# Project.net
KiCad netlist of a schematic drawn in EAGLE
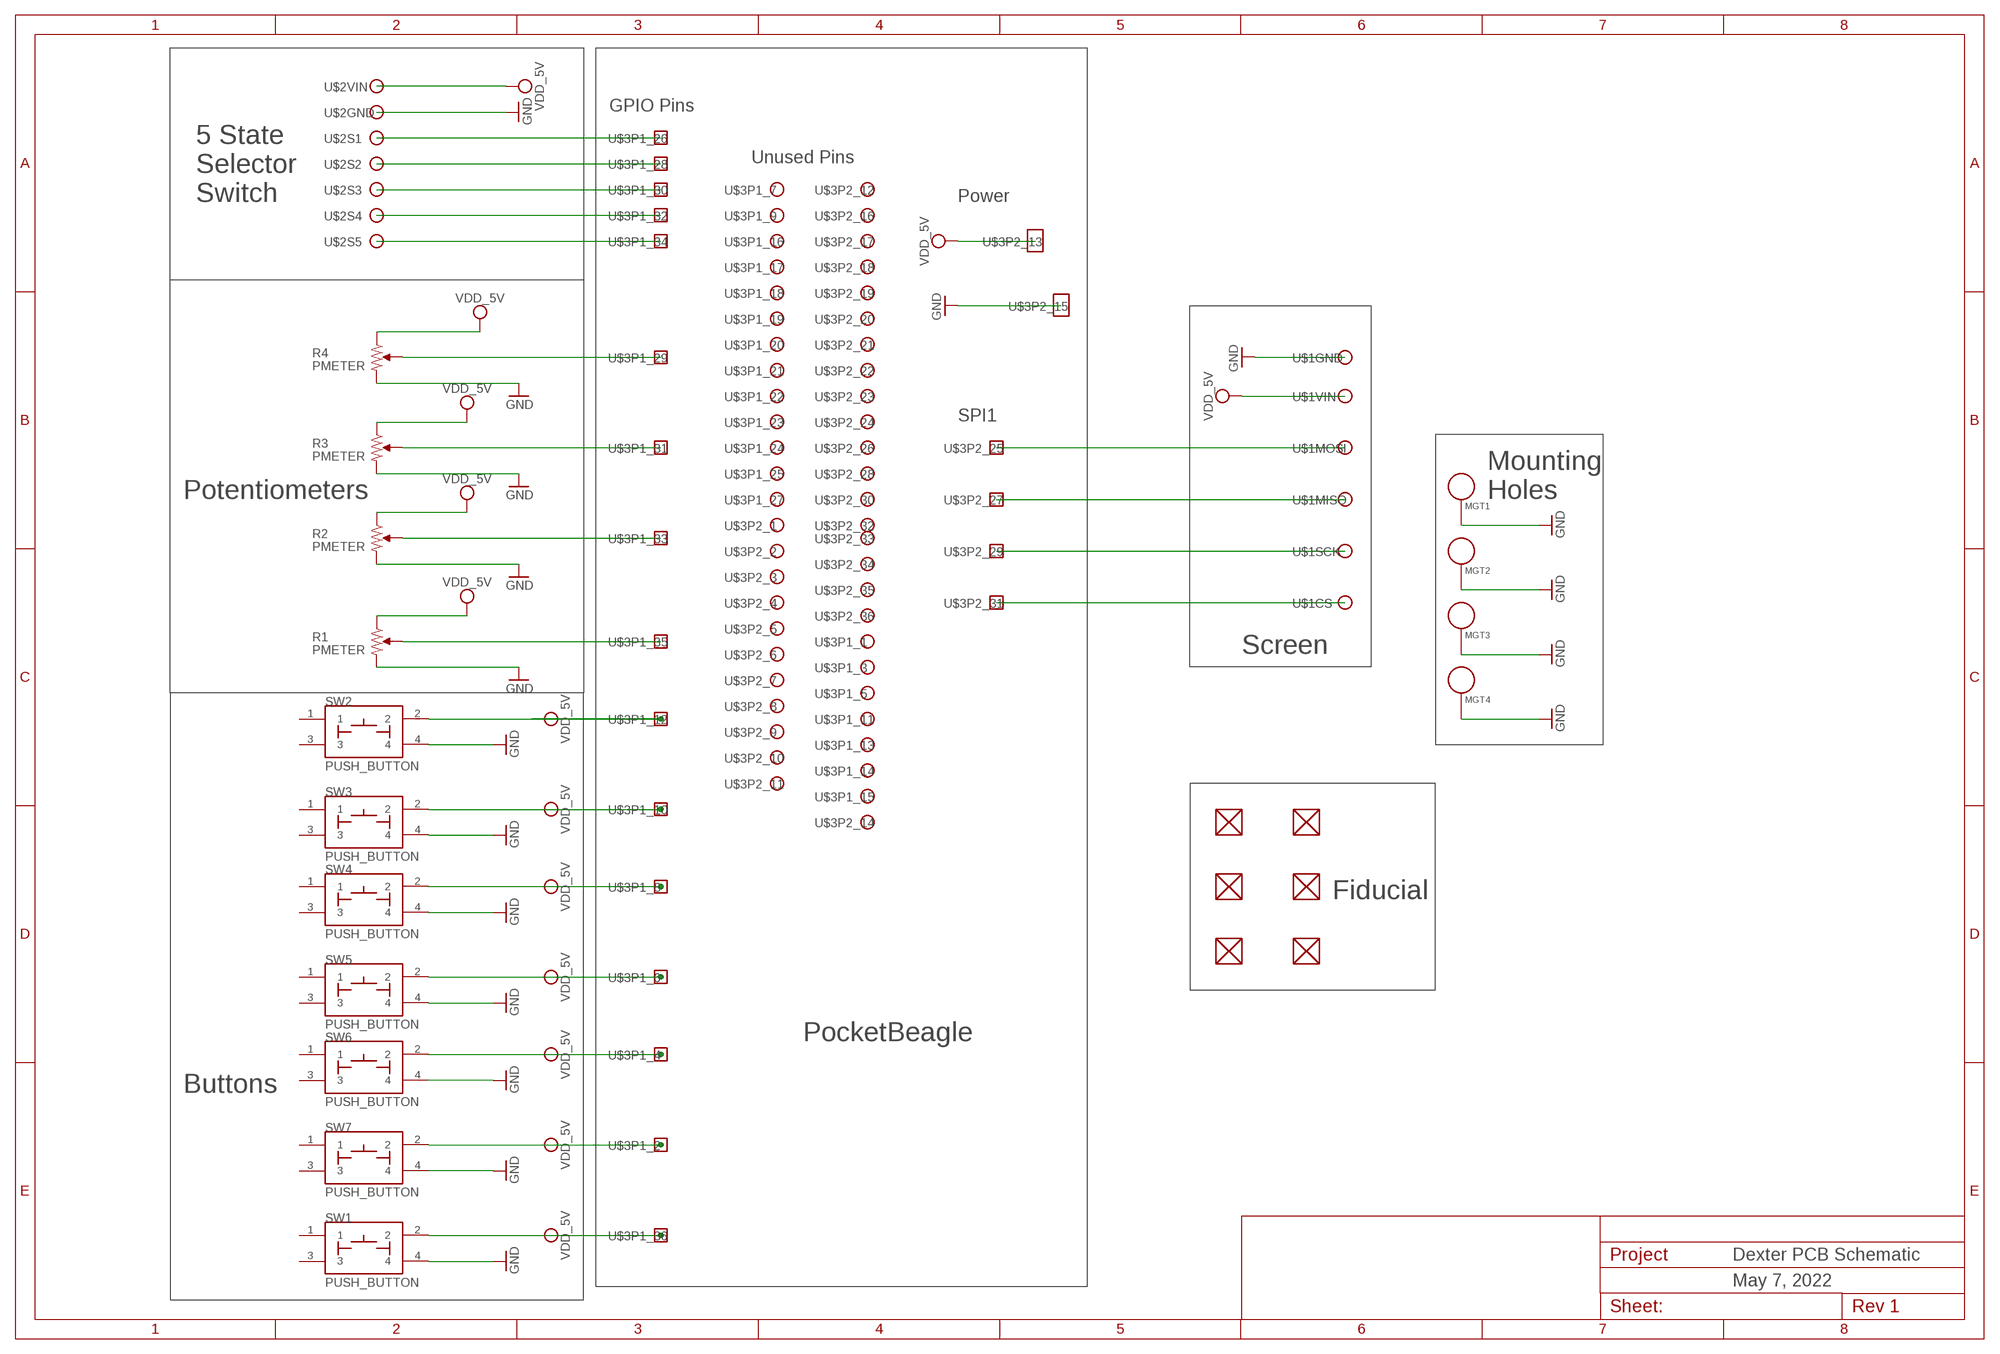
[diagram p0: schematic, sheet 1]

(export (version "E")
  (design (tool "Eeschema 10.0.6"))
  (components
    (comp (ref "FUD1")
      (value "FIDUCIAL")
      (footprint "eagle-import:FIDUCIAL_40MIL")
      (libsource (lib "eagle-import") (part "FIDUCIAL"))
    )
    (comp (ref "FUD2")
      (value "FIDUCIAL")
      (footprint "eagle-import:FIDUCIAL_40MIL")
      (libsource (lib "eagle-import") (part "FIDUCIAL"))
    )
    (comp (ref "FUD3")
      (value "FIDUCIAL")
      (footprint "eagle-import:FIDUCIAL_40MIL")
      (libsource (lib "eagle-import") (part "FIDUCIAL"))
    )
    (comp (ref "FUD4")
      (value "FIDUCIAL")
      (footprint "eagle-import:FIDUCIAL_40MIL")
      (libsource (lib "eagle-import") (part "FIDUCIAL"))
    )
    (comp (ref "FUD5")
      (value "FIDUCIAL")
      (footprint "eagle-import:FIDUCIAL_40MIL")
      (libsource (lib "eagle-import") (part "FIDUCIAL"))
    )
    (comp (ref "FUD6")
      (value "FIDUCIAL")
      (footprint "eagle-import:FIDUCIAL_40MIL")
      (libsource (lib "eagle-import") (part "FIDUCIAL"))
    )
    (comp (ref "MGT1")
      (value "MOUNTING_HOLE")
      (footprint "eagle-import:MOUNTING_HOLE")
      (libsource (lib "eagle-import") (part "MOUNTING_HOLE"))
    )
    (comp (ref "MGT2")
      (value "MOUNTING_HOLE")
      (footprint "eagle-import:MOUNTING_HOLE")
      (libsource (lib "eagle-import") (part "MOUNTING_HOLE"))
    )
    (comp (ref "MGT3")
      (value "MOUNTING_HOLE")
      (footprint "eagle-import:MOUNTING_HOLE")
      (libsource (lib "eagle-import") (part "MOUNTING_HOLE"))
    )
    (comp (ref "MGT4")
      (value "MOUNTING_HOLE")
      (footprint "eagle-import:MOUNTING_HOLE")
      (libsource (lib "eagle-import") (part "MOUNTING_HOLE"))
    )
    (comp (ref "R1")
      (value "PMETER")
      (footprint "eagle-import:POT-PO90S")
      (libsource (lib "eagle-import") (part "PMETER"))
    )
    (comp (ref "R2")
      (value "PMETER")
      (footprint "eagle-import:POT-PO90S")
      (libsource (lib "eagle-import") (part "PMETER"))
    )
    (comp (ref "R3")
      (value "PMETER")
      (footprint "eagle-import:POT-PO90S")
      (libsource (lib "eagle-import") (part "PMETER"))
    )
    (comp (ref "R4")
      (value "PMETER")
      (footprint "eagle-import:POT-PO90S")
      (libsource (lib "eagle-import") (part "PMETER"))
    )
    (comp (ref "SW1")
      (value "PUSH_BUTTON")
      (footprint "eagle-import:BUTTON_12.5MM")
      (libsource (lib "eagle-import") (part "PUSH_BUTTON"))
    )
    (comp (ref "SW2")
      (value "PUSH_BUTTON")
      (footprint "eagle-import:BUTTON_12.5MM")
      (libsource (lib "eagle-import") (part "PUSH_BUTTON"))
    )
    (comp (ref "SW3")
      (value "PUSH_BUTTON")
      (footprint "eagle-import:BUTTON_12.5MM")
      (libsource (lib "eagle-import") (part "PUSH_BUTTON"))
    )
    (comp (ref "SW4")
      (value "PUSH_BUTTON")
      (footprint "eagle-import:BUTTON_12.5MM")
      (libsource (lib "eagle-import") (part "PUSH_BUTTON"))
    )
    (comp (ref "SW5")
      (value "PUSH_BUTTON")
      (footprint "eagle-import:BUTTON_12.5MM")
      (libsource (lib "eagle-import") (part "PUSH_BUTTON"))
    )
    (comp (ref "SW6")
      (value "PUSH_BUTTON")
      (footprint "eagle-import:BUTTON_12.5MM")
      (libsource (lib "eagle-import") (part "PUSH_BUTTON"))
    )
    (comp (ref "SW7")
      (value "PUSH_BUTTON")
      (footprint "eagle-import:BUTTON_12.5MM")
      (libsource (lib "eagle-import") (part "PUSH_BUTTON"))
    )
    (comp (ref "U$1")
      (value "SCREEN")
      (footprint "eagle-import:SCREEN")
      (libsource (lib "eagle-import") (part "SCREEN"))
    )
    (comp (ref "U$2")
      (value "SELECTOR_SWITCH")
      (footprint "eagle-import:SELECTOR_SWITCH")
      (libsource (lib "eagle-import") (part "SELECTOR_SWITCH"))
    )
    (comp (ref "U$3")
      (value "POCKETBEAGLE")
      (footprint "eagle-import:POCKETBEAGLE")
      (libsource (lib "eagle-import") (part "POCKETBEAGLE"))
    )
  )
  (nets
    (net (code "1") (name "GND") (class "Default")
      (node (ref "MGT1") (pin "P$1") (pinfunction "P$1_P$1") (pintype "bidirectional"))
      (node (ref "MGT2") (pin "P$1") (pinfunction "P$1_P$1") (pintype "bidirectional"))
      (node (ref "MGT3") (pin "P$1") (pinfunction "P$1_P$1") (pintype "bidirectional"))
      (node (ref "MGT4") (pin "P$1") (pinfunction "P$1_P$1") (pintype "bidirectional"))
      (node (ref "R1") (pin "CW") (pinfunction "CW_CW") (pintype "passive"))
      (node (ref "R2") (pin "CW") (pinfunction "CW_CW") (pintype "passive"))
      (node (ref "R3") (pin "CW") (pinfunction "CW_CW") (pintype "passive"))
      (node (ref "R4") (pin "CW") (pinfunction "CW_CW") (pintype "passive"))
      (node (ref "SW1") (pin "4") (pinfunction "4_4") (pintype "bidirectional"))
      (node (ref "SW2") (pin "4") (pinfunction "4_4") (pintype "bidirectional"))
      (node (ref "SW3") (pin "4") (pinfunction "4_4") (pintype "bidirectional"))
      (node (ref "SW4") (pin "4") (pinfunction "4_4") (pintype "bidirectional"))
      (node (ref "SW5") (pin "4") (pinfunction "4_4") (pintype "bidirectional"))
      (node (ref "SW6") (pin "4") (pinfunction "4_4") (pintype "bidirectional"))
      (node (ref "SW7") (pin "4") (pinfunction "4_4") (pintype "bidirectional"))
      (node (ref "U$1") (pin "1@JP1") (pinfunction "PWR_1@JP1") (pintype "bidirectional"))
      (node (ref "U$2") (pin "P$2") (pinfunction "PWR_P$2") (pintype "bidirectional"))
      (node (ref "U$3") (pin "15@P2") (pinfunction "PWR_15@P2") (pintype "bidirectional"))
    )
    (net (code "2") (name "Net-(U$1A-PWR)") (class "Default")
      (node (ref "U$1") (pin "5@JP1") (pinfunction "PWR_5@JP1") (pintype "bidirectional"))
      (node (ref "U$3") (pin "31@P2") (pinfunction "PWR_31@P2") (pintype "bidirectional"))
    )
    (net (code "3") (name "Net-(U$1C-PWR)") (class "Default")
      (node (ref "U$1") (pin "7@JP1") (pinfunction "PWR_7@JP1") (pintype "bidirectional"))
      (node (ref "U$3") (pin "27@P2") (pinfunction "PWR_27@P2") (pintype "bidirectional"))
    )
    (net (code "4") (name "Net-(U$1D-PWR)") (class "Default")
      (node (ref "U$1") (pin "6@JP1") (pinfunction "PWR_6@JP1") (pintype "bidirectional"))
      (node (ref "U$3") (pin "25@P2") (pinfunction "PWR_25@P2") (pintype "bidirectional"))
    )
    (net (code "5") (name "Net-(U$1E-PWR)") (class "Default")
      (node (ref "U$1") (pin "8@JP1") (pinfunction "PWR_8@JP1") (pintype "bidirectional"))
      (node (ref "U$3") (pin "29@P2") (pinfunction "PWR_29@P2") (pintype "bidirectional"))
    )
    (net (code "6") (name "Net-(U$2B-PWR)") (class "Default")
      (node (ref "U$2") (pin "P$3") (pinfunction "PWR_P$3") (pintype "bidirectional"))
      (node (ref "U$3") (pin "26@P1") (pinfunction "PWR_26@P1") (pintype "bidirectional"))
    )
    (net (code "7") (name "Net-(U$2C-PWR)") (class "Default")
      (node (ref "U$2") (pin "P$4") (pinfunction "PWR_P$4") (pintype "bidirectional"))
      (node (ref "U$3") (pin "28@P1") (pinfunction "PWR_28@P1") (pintype "bidirectional"))
    )
    (net (code "8") (name "Net-(U$2D-PWR)") (class "Default")
      (node (ref "U$2") (pin "P$5") (pinfunction "PWR_P$5") (pintype "bidirectional"))
      (node (ref "U$3") (pin "30@P1") (pinfunction "PWR_30@P1") (pintype "bidirectional"))
    )
    (net (code "9") (name "Net-(U$2E-PWR)") (class "Default")
      (node (ref "U$2") (pin "P$6") (pinfunction "PWR_P$6") (pintype "bidirectional"))
      (node (ref "U$3") (pin "32@P1") (pinfunction "PWR_32@P1") (pintype "bidirectional"))
    )
    (net (code "10") (name "Net-(U$2F-PWR)") (class "Default")
      (node (ref "U$2") (pin "P$7") (pinfunction "PWR_P$7") (pintype "bidirectional"))
      (node (ref "U$3") (pin "34@P1") (pinfunction "PWR_34@P1") (pintype "bidirectional"))
    )
    (net (code "11") (name "Net-(U$3AA-PWR)") (class "Default")
      (node (ref "R2") (pin "S") (pinfunction "S_S") (pintype "bidirectional"))
      (node (ref "U$3") (pin "33@P1") (pinfunction "PWR_33@P1") (pintype "bidirectional"))
    )
    (net (code "12") (name "Net-(U$3AC-PWR)") (class "Default")
      (node (ref "R1") (pin "S") (pinfunction "S_S") (pintype "bidirectional"))
      (node (ref "U$3") (pin "35@P1") (pinfunction "PWR_35@P1") (pintype "bidirectional"))
    )
    (net (code "13") (name "Net-(U$3V-PWR)") (class "Default")
      (node (ref "R4") (pin "S") (pinfunction "S_S") (pintype "bidirectional"))
      (node (ref "U$3") (pin "29@P1") (pinfunction "PWR_29@P1") (pintype "bidirectional"))
    )
    (net (code "14") (name "Net-(U$3Y-PWR)") (class "Default")
      (node (ref "R3") (pin "S") (pinfunction "S_S") (pintype "bidirectional"))
      (node (ref "U$3") (pin "31@P1") (pinfunction "PWR_31@P1") (pintype "bidirectional"))
    )
    (net (code "15") (name "VDD_5V") (class "Default")
      (node (ref "R1") (pin "CCW") (pinfunction "CCW_CCW") (pintype "passive"))
      (node (ref "R2") (pin "CCW") (pinfunction "CCW_CCW") (pintype "passive"))
      (node (ref "R3") (pin "CCW") (pinfunction "CCW_CCW") (pintype "passive"))
      (node (ref "R4") (pin "CCW") (pinfunction "CCW_CCW") (pintype "passive"))
      (node (ref "SW1") (pin "2") (pinfunction "2_2") (pintype "bidirectional"))
      (node (ref "SW2") (pin "2") (pinfunction "2_2") (pintype "bidirectional"))
      (node (ref "SW3") (pin "2") (pinfunction "2_2") (pintype "bidirectional"))
      (node (ref "SW4") (pin "2") (pinfunction "2_2") (pintype "bidirectional"))
      (node (ref "SW5") (pin "2") (pinfunction "2_2") (pintype "bidirectional"))
      (node (ref "SW6") (pin "2") (pinfunction "2_2") (pintype "bidirectional"))
      (node (ref "SW7") (pin "2") (pinfunction "2_2") (pintype "bidirectional"))
      (node (ref "U$1") (pin "2@JP1") (pinfunction "PWR_2@JP1") (pintype "bidirectional"))
      (node (ref "U$2") (pin "P$1") (pinfunction "PWR_P$1") (pintype "bidirectional"))
      (node (ref "U$3") (pin "10@P1") (pinfunction "PWR_10@P1") (pintype "bidirectional"))
      (node (ref "U$3") (pin "12@P1") (pinfunction "PWR_12@P1") (pintype "bidirectional"))
      (node (ref "U$3") (pin "13@P2") (pinfunction "PWR_13@P2") (pintype "bidirectional"))
      (node (ref "U$3") (pin "2@P1") (pinfunction "PWR_2@P1") (pintype "bidirectional"))
      (node (ref "U$3") (pin "36@P1") (pinfunction "PWR_36@P1") (pintype "bidirectional"))
      (node (ref "U$3") (pin "4@P1") (pinfunction "PWR_4@P1") (pintype "bidirectional"))
      (node (ref "U$3") (pin "6@P1") (pinfunction "PWR_6@P1") (pintype "bidirectional"))
      (node (ref "U$3") (pin "8@P1") (pinfunction "PWR_8@P1") (pintype "bidirectional"))
    )
    (net (code "16") (name "unconnected-(FUD1-PadP$1)") (class "Default")
      (node (ref "FUD1") (pin "P$1") (pinfunction "P$1_P$1") (pintype "no_connect"))
    )
    (net (code "17") (name "unconnected-(FUD2-PadP$1)") (class "Default")
      (node (ref "FUD2") (pin "P$1") (pinfunction "P$1_P$1") (pintype "no_connect"))
    )
    (net (code "18") (name "unconnected-(FUD3-PadP$1)") (class "Default")
      (node (ref "FUD3") (pin "P$1") (pinfunction "P$1_P$1") (pintype "no_connect"))
    )
    (net (code "19") (name "unconnected-(FUD4-PadP$1)") (class "Default")
      (node (ref "FUD4") (pin "P$1") (pinfunction "P$1_P$1") (pintype "no_connect"))
    )
    (net (code "20") (name "unconnected-(FUD5-PadP$1)") (class "Default")
      (node (ref "FUD5") (pin "P$1") (pinfunction "P$1_P$1") (pintype "no_connect"))
    )
    (net (code "21") (name "unconnected-(FUD6-PadP$1)") (class "Default")
      (node (ref "FUD6") (pin "P$1") (pinfunction "P$1_P$1") (pintype "no_connect"))
    )
    (net (code "22") (name "unconnected-(SW1-Pad1)") (class "Default")
      (node (ref "SW1") (pin "1") (pinfunction "1_1") (pintype "bidirectional"))
    )
    (net (code "23") (name "unconnected-(SW1-Pad3)") (class "Default")
      (node (ref "SW1") (pin "3") (pinfunction "3_3") (pintype "bidirectional"))
    )
    (net (code "24") (name "unconnected-(SW2-Pad1)") (class "Default")
      (node (ref "SW2") (pin "1") (pinfunction "1_1") (pintype "bidirectional"))
    )
    (net (code "25") (name "unconnected-(SW2-Pad3)") (class "Default")
      (node (ref "SW2") (pin "3") (pinfunction "3_3") (pintype "bidirectional"))
    )
    (net (code "26") (name "unconnected-(SW3-Pad1)") (class "Default")
      (node (ref "SW3") (pin "1") (pinfunction "1_1") (pintype "bidirectional"))
    )
    (net (code "27") (name "unconnected-(SW3-Pad3)") (class "Default")
      (node (ref "SW3") (pin "3") (pinfunction "3_3") (pintype "bidirectional"))
    )
    (net (code "28") (name "unconnected-(SW4-Pad1)") (class "Default")
      (node (ref "SW4") (pin "1") (pinfunction "1_1") (pintype "bidirectional"))
    )
    (net (code "29") (name "unconnected-(SW4-Pad3)") (class "Default")
      (node (ref "SW4") (pin "3") (pinfunction "3_3") (pintype "bidirectional"))
    )
    (net (code "30") (name "unconnected-(SW5-Pad1)") (class "Default")
      (node (ref "SW5") (pin "1") (pinfunction "1_1") (pintype "bidirectional"))
    )
    (net (code "31") (name "unconnected-(SW5-Pad3)") (class "Default")
      (node (ref "SW5") (pin "3") (pinfunction "3_3") (pintype "bidirectional"))
    )
    (net (code "32") (name "unconnected-(SW6-Pad1)") (class "Default")
      (node (ref "SW6") (pin "1") (pinfunction "1_1") (pintype "bidirectional"))
    )
    (net (code "33") (name "unconnected-(SW6-Pad3)") (class "Default")
      (node (ref "SW6") (pin "3") (pinfunction "3_3") (pintype "bidirectional"))
    )
    (net (code "34") (name "unconnected-(SW7-Pad1)") (class "Default")
      (node (ref "SW7") (pin "1") (pinfunction "1_1") (pintype "bidirectional"))
    )
    (net (code "35") (name "unconnected-(SW7-Pad3)") (class "Default")
      (node (ref "SW7") (pin "3") (pinfunction "3_3") (pintype "bidirectional"))
    )
    (net (code "36") (name "unconnected-(U$3A-PWR-Pad1@P1)") (class "Default")
      (node (ref "U$3") (pin "1@P1") (pinfunction "PWR_1@P1") (pintype "bidirectional"))
    )
    (net (code "37") (name "unconnected-(U$3AF-PWR-Pad5@P1)") (class "Default")
      (node (ref "U$3") (pin "5@P1") (pinfunction "PWR_5@P1") (pintype "bidirectional"))
    )
    (net (code "38") (name "unconnected-(U$3AH-PWR-Pad7@P1)") (class "Default")
      (node (ref "U$3") (pin "7@P1") (pinfunction "PWR_7@P1") (pintype "bidirectional"))
    )
    (net (code "39") (name "unconnected-(U$3AJ-PWR-Pad9@P1)") (class "Default")
      (node (ref "U$3") (pin "9@P1") (pinfunction "PWR_9@P1") (pintype "bidirectional"))
    )
    (net (code "40") (name "unconnected-(U$3AK-PWR-Pad1@P2)") (class "Default")
      (node (ref "U$3") (pin "1@P2") (pinfunction "PWR_1@P2") (pintype "bidirectional"))
    )
    (net (code "41") (name "unconnected-(U$3AL-PWR-Pad10@P2)") (class "Default")
      (node (ref "U$3") (pin "10@P2") (pinfunction "PWR_10@P2") (pintype "bidirectional"))
    )
    (net (code "42") (name "unconnected-(U$3AM-PWR-Pad11@P2)") (class "Default")
      (node (ref "U$3") (pin "11@P2") (pinfunction "PWR_11@P2") (pintype "bidirectional"))
    )
    (net (code "43") (name "unconnected-(U$3AN-PWR-Pad12@P2)") (class "Default")
      (node (ref "U$3") (pin "12@P2") (pinfunction "PWR_12@P2") (pintype "bidirectional"))
    )
    (net (code "44") (name "unconnected-(U$3AP-PWR-Pad14@P2)") (class "Default")
      (node (ref "U$3") (pin "14@P2") (pinfunction "PWR_14@P2") (pintype "bidirectional"))
    )
    (net (code "45") (name "unconnected-(U$3AR-PWR-Pad16@P2)") (class "Default")
      (node (ref "U$3") (pin "16@P2") (pinfunction "PWR_16@P2") (pintype "bidirectional"))
    )
    (net (code "46") (name "unconnected-(U$3AS-PWR-Pad17@P2)") (class "Default")
      (node (ref "U$3") (pin "17@P2") (pinfunction "PWR_17@P2") (pintype "bidirectional"))
    )
    (net (code "47") (name "unconnected-(U$3AT-PWR-Pad18@P2)") (class "Default")
      (node (ref "U$3") (pin "18@P2") (pinfunction "PWR_18@P2") (pintype "bidirectional"))
    )
    (net (code "48") (name "unconnected-(U$3AU-PWR-Pad19@P2)") (class "Default")
      (node (ref "U$3") (pin "19@P2") (pinfunction "PWR_19@P2") (pintype "bidirectional"))
    )
    (net (code "49") (name "unconnected-(U$3AV-PWR-Pad2@P2)") (class "Default")
      (node (ref "U$3") (pin "2@P2") (pinfunction "PWR_2@P2") (pintype "bidirectional"))
    )
    (net (code "50") (name "unconnected-(U$3AW-PWR-Pad20@P2)") (class "Default")
      (node (ref "U$3") (pin "20@P2") (pinfunction "PWR_20@P2") (pintype "bidirectional"))
    )
    (net (code "51") (name "unconnected-(U$3AX-PWR-Pad21@P2)") (class "Default")
      (node (ref "U$3") (pin "21@P2") (pinfunction "PWR_21@P2") (pintype "bidirectional"))
    )
    (net (code "52") (name "unconnected-(U$3AY-PWR-Pad22@P2)") (class "Default")
      (node (ref "U$3") (pin "22@P2") (pinfunction "PWR_22@P2") (pintype "bidirectional"))
    )
    (net (code "53") (name "unconnected-(U$3AZ-PWR-Pad23@P2)") (class "Default")
      (node (ref "U$3") (pin "23@P2") (pinfunction "PWR_23@P2") (pintype "bidirectional"))
    )
    (net (code "54") (name "unconnected-(U$3BA-PWR-Pad24@P2)") (class "Default")
      (node (ref "U$3") (pin "24@P2") (pinfunction "PWR_24@P2") (pintype "bidirectional"))
    )
    (net (code "55") (name "unconnected-(U$3BC-PWR-Pad26@P2)") (class "Default")
      (node (ref "U$3") (pin "26@P2") (pinfunction "PWR_26@P2") (pintype "bidirectional"))
    )
    (net (code "56") (name "unconnected-(U$3BE-PWR-Pad28@P2)") (class "Default")
      (node (ref "U$3") (pin "28@P2") (pinfunction "PWR_28@P2") (pintype "bidirectional"))
    )
    (net (code "57") (name "unconnected-(U$3BG-PWR-Pad3@P2)") (class "Default")
      (node (ref "U$3") (pin "3@P2") (pinfunction "PWR_3@P2") (pintype "bidirectional"))
    )
    (net (code "58") (name "unconnected-(U$3BH-PWR-Pad30@P2)") (class "Default")
      (node (ref "U$3") (pin "30@P2") (pinfunction "PWR_30@P2") (pintype "bidirectional"))
    )
    (net (code "59") (name "unconnected-(U$3BJ-PWR-Pad32@P2)") (class "Default")
      (node (ref "U$3") (pin "32@P2") (pinfunction "PWR_32@P2") (pintype "bidirectional"))
    )
    (net (code "60") (name "unconnected-(U$3BK-PWR-Pad33@P2)") (class "Default")
      (node (ref "U$3") (pin "33@P2") (pinfunction "PWR_33@P2") (pintype "bidirectional"))
    )
    (net (code "61") (name "unconnected-(U$3BL-PWR-Pad34@P2)") (class "Default")
      (node (ref "U$3") (pin "34@P2") (pinfunction "PWR_34@P2") (pintype "bidirectional"))
    )
    (net (code "62") (name "unconnected-(U$3BM-PWR-Pad35@P2)") (class "Default")
      (node (ref "U$3") (pin "35@P2") (pinfunction "PWR_35@P2") (pintype "bidirectional"))
    )
    (net (code "63") (name "unconnected-(U$3BN-PWR-Pad36@P2)") (class "Default")
      (node (ref "U$3") (pin "36@P2") (pinfunction "PWR_36@P2") (pintype "bidirectional"))
    )
    (net (code "64") (name "unconnected-(U$3BO-PWR-Pad4@P2)") (class "Default")
      (node (ref "U$3") (pin "4@P2") (pinfunction "PWR_4@P2") (pintype "bidirectional"))
    )
    (net (code "65") (name "unconnected-(U$3BP-PWR-Pad5@P2)") (class "Default")
      (node (ref "U$3") (pin "5@P2") (pinfunction "PWR_5@P2") (pintype "bidirectional"))
    )
    (net (code "66") (name "unconnected-(U$3BQ-PWR-Pad6@P2)") (class "Default")
      (node (ref "U$3") (pin "6@P2") (pinfunction "PWR_6@P2") (pintype "bidirectional"))
    )
    (net (code "67") (name "unconnected-(U$3BR-PWR-Pad7@P2)") (class "Default")
      (node (ref "U$3") (pin "7@P2") (pinfunction "PWR_7@P2") (pintype "bidirectional"))
    )
    (net (code "68") (name "unconnected-(U$3BS-PWR-Pad8@P2)") (class "Default")
      (node (ref "U$3") (pin "8@P2") (pinfunction "PWR_8@P2") (pintype "bidirectional"))
    )
    (net (code "69") (name "unconnected-(U$3BT-PWR-Pad9@P2)") (class "Default")
      (node (ref "U$3") (pin "9@P2") (pinfunction "PWR_9@P2") (pintype "bidirectional"))
    )
    (net (code "70") (name "unconnected-(U$3C-PWR-Pad11@P1)") (class "Default")
      (node (ref "U$3") (pin "11@P1") (pinfunction "PWR_11@P1") (pintype "bidirectional"))
    )
    (net (code "71") (name "unconnected-(U$3E-PWR-Pad13@P1)") (class "Default")
      (node (ref "U$3") (pin "13@P1") (pinfunction "PWR_13@P1") (pintype "bidirectional"))
    )
    (net (code "72") (name "unconnected-(U$3F-PWR-Pad14@P1)") (class "Default")
      (node (ref "U$3") (pin "14@P1") (pinfunction "PWR_14@P1") (pintype "bidirectional"))
    )
    (net (code "73") (name "unconnected-(U$3G-PWR-Pad15@P1)") (class "Default")
      (node (ref "U$3") (pin "15@P1") (pinfunction "PWR_15@P1") (pintype "bidirectional"))
    )
    (net (code "74") (name "unconnected-(U$3H-PWR-Pad16@P1)") (class "Default")
      (node (ref "U$3") (pin "16@P1") (pinfunction "PWR_16@P1") (pintype "bidirectional"))
    )
    (net (code "75") (name "unconnected-(U$3I-PWR-Pad17@P1)") (class "Default")
      (node (ref "U$3") (pin "17@P1") (pinfunction "PWR_17@P1") (pintype "bidirectional"))
    )
    (net (code "76") (name "unconnected-(U$3J-PWR-Pad18@P1)") (class "Default")
      (node (ref "U$3") (pin "18@P1") (pinfunction "PWR_18@P1") (pintype "bidirectional"))
    )
    (net (code "77") (name "unconnected-(U$3K-PWR-Pad19@P1)") (class "Default")
      (node (ref "U$3") (pin "19@P1") (pinfunction "PWR_19@P1") (pintype "bidirectional"))
    )
    (net (code "78") (name "unconnected-(U$3M-PWR-Pad20@P1)") (class "Default")
      (node (ref "U$3") (pin "20@P1") (pinfunction "PWR_20@P1") (pintype "bidirectional"))
    )
    (net (code "79") (name "unconnected-(U$3N-PWR-Pad21@P1)") (class "Default")
      (node (ref "U$3") (pin "21@P1") (pinfunction "PWR_21@P1") (pintype "bidirectional"))
    )
    (net (code "80") (name "unconnected-(U$3O-PWR-Pad22@P1)") (class "Default")
      (node (ref "U$3") (pin "22@P1") (pinfunction "PWR_22@P1") (pintype "bidirectional"))
    )
    (net (code "81") (name "unconnected-(U$3P-PWR-Pad23@P1)") (class "Default")
      (node (ref "U$3") (pin "23@P1") (pinfunction "PWR_23@P1") (pintype "bidirectional"))
    )
    (net (code "82") (name "unconnected-(U$3Q-PWR-Pad24@P1)") (class "Default")
      (node (ref "U$3") (pin "24@P1") (pinfunction "PWR_24@P1") (pintype "bidirectional"))
    )
    (net (code "83") (name "unconnected-(U$3R-PWR-Pad25@P1)") (class "Default")
      (node (ref "U$3") (pin "25@P1") (pinfunction "PWR_25@P1") (pintype "bidirectional"))
    )
    (net (code "84") (name "unconnected-(U$3T-PWR-Pad27@P1)") (class "Default")
      (node (ref "U$3") (pin "27@P1") (pinfunction "PWR_27@P1") (pintype "bidirectional"))
    )
    (net (code "85") (name "unconnected-(U$3W-PWR-Pad3@P1)") (class "Default")
      (node (ref "U$3") (pin "3@P1") (pinfunction "PWR_3@P1") (pintype "bidirectional"))
    )
  )
)
